# power.net
KiCad netlist of a schematic drawn in Altium Designer
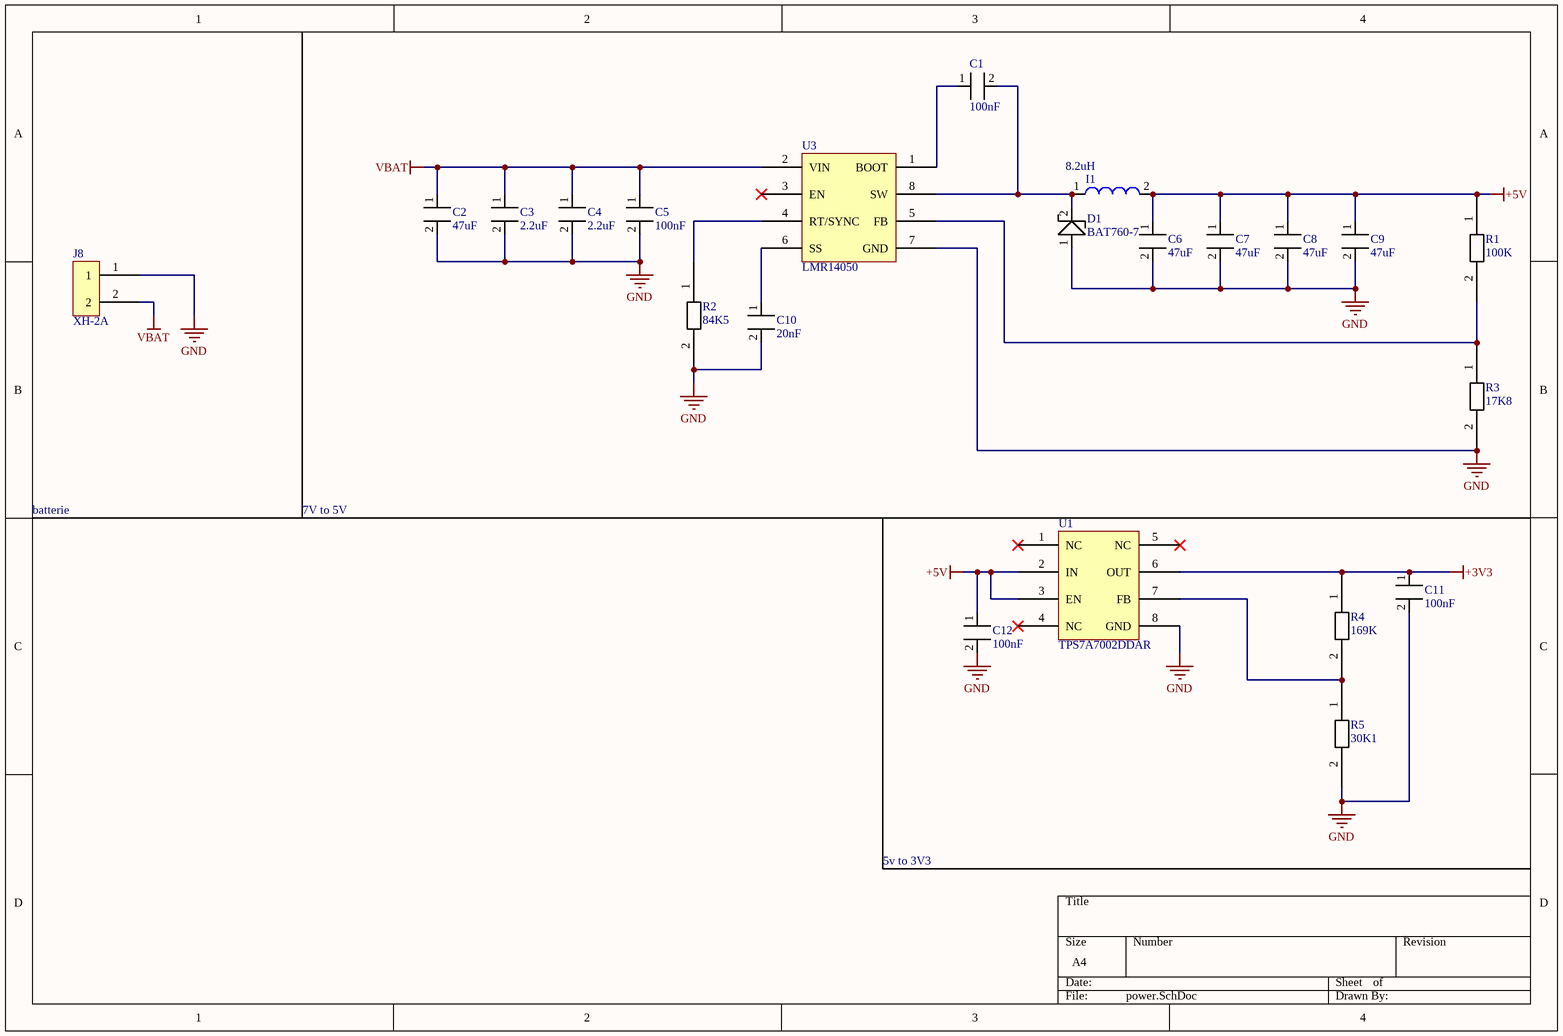
[diagram p0: power.SchDoc]

(export (version "E")
  (design (tool "Eeschema 10.0.6"))
  (components
    (comp (ref "C1") (value "100nF") (footprint "Condo") (libsource (lib "Schlib1") (part "CAPA")))
    (comp (ref "C2") (value "47uF") (footprint "Condo") (libsource (lib "Schlib1") (part "CAPA")))
    (comp (ref "C3") (value "2.2uF") (footprint "Condo") (libsource (lib "Schlib1") (part "CAPA")))
    (comp (ref "C4") (value "2.2uF") (footprint "Condo") (libsource (lib "Schlib1") (part "CAPA")))
    (comp (ref "C5") (value "100nF") (footprint "Condo") (libsource (lib "Schlib1") (part "CAPA")))
    (comp (ref "C6") (value "47uF") (footprint "Condo") (libsource (lib "Schlib1") (part "CAPA")))
    (comp (ref "C7") (value "47uF") (footprint "Condo") (libsource (lib "Schlib1") (part "CAPA")))
    (comp (ref "C8") (value "47uF") (footprint "Condo") (libsource (lib "Schlib1") (part "CAPA")))
    (comp (ref "C9") (value "47uF") (footprint "Condo") (libsource (lib "Schlib1") (part "CAPA")))
    (comp (ref "C10") (value "20nF") (footprint "Condo") (libsource (lib "Schlib1") (part "CAPA")))
    (comp (ref "C11") (value "100nF") (footprint "Condo") (libsource (lib "Schlib1") (part "CAPA")))
    (comp (ref "C12") (value "100nF") (footprint "Condo") (libsource (lib "Schlib1") (part "CAPA")))
    (comp (ref "D1") (value "BAT760-7") (footprint "BAT760-7") (libsource (lib "Schlib1") (part "BAT760-7")))
    (comp (ref "I1")
      (value "8.2uH")
      (footprint "ILSB0805ER8R2K")
      (description "ILSB0805ER8R2K")
      (libsource (lib "Schlib1") (part "ILSB0805ER8R2K"))
    )
    (comp (ref "J8") (value "XH-2A") (footprint "XH-2A") (libsource (lib "Schlib1") (part "XH-2A")))
    (comp (ref "R1") (value "100K") (footprint "Resistor") (libsource (lib "Schlib1") (part "Resistor")))
    (comp (ref "R2") (value "84K5") (footprint "Resistor") (libsource (lib "Schlib1") (part "Resistor")))
    (comp (ref "R3") (value "17K8") (footprint "Resistor") (libsource (lib "Schlib1") (part "Resistor")))
    (comp (ref "R4") (value "169K") (footprint "Resistor") (libsource (lib "Schlib1") (part "Resistor")))
    (comp (ref "R5") (value "30K1") (footprint "Resistor") (libsource (lib "Schlib1") (part "Resistor")))
    (comp (ref "U1")
      (value "TPS7A7002DDAR")
      (footprint "TPS7A7002DDAR")
      (libsource (lib "Schlib1") (part "TPS7A7002DDAR"))
    )
    (comp (ref "U3") (value "LMR14050") (footprint "LMR14050") (libsource (lib "Schlib1") (part "LMR14050")))
  )
  (nets
    (net (code "1") (name "+3V3") (class "Default")
      (node (ref "C11") (pin "1") (pinfunction "IN_1") (pintype "passive"))
      (node (ref "R4") (pin "1") (pinfunction "1_1") (pintype "passive"))
      (node (ref "U1") (pin "6") (pinfunction "OUT_6") (pintype "passive"))
    )
    (net (code "2") (name "+5V") (class "Default")
      (node (ref "C12") (pin "1") (pinfunction "IN_1") (pintype "passive"))
      (node (ref "C6") (pin "1") (pinfunction "IN_1") (pintype "passive"))
      (node (ref "C7") (pin "1") (pinfunction "IN_1") (pintype "passive"))
      (node (ref "C8") (pin "1") (pinfunction "IN_1") (pintype "passive"))
      (node (ref "C9") (pin "1") (pinfunction "IN_1") (pintype "passive"))
      (node (ref "I1") (pin "2") (pinfunction "2_2") (pintype "passive"))
      (node (ref "R1") (pin "1") (pinfunction "1_1") (pintype "passive"))
      (node (ref "U1") (pin "2") (pinfunction "IN_2") (pintype "passive"))
      (node (ref "U1") (pin "3") (pinfunction "EN_3") (pintype "passive"))
    )
    (net (code "3") (name "GND") (class "Default")
      (node (ref "C10") (pin "2") (pinfunction "OUT_2") (pintype "passive"))
      (node (ref "C11") (pin "2") (pinfunction "OUT_2") (pintype "passive"))
      (node (ref "C12") (pin "2") (pinfunction "OUT_2") (pintype "passive"))
      (node (ref "C2") (pin "2") (pinfunction "OUT_2") (pintype "passive"))
      (node (ref "C3") (pin "2") (pinfunction "OUT_2") (pintype "passive"))
      (node (ref "C4") (pin "2") (pinfunction "OUT_2") (pintype "passive"))
      (node (ref "C5") (pin "2") (pinfunction "OUT_2") (pintype "passive"))
      (node (ref "C6") (pin "2") (pinfunction "OUT_2") (pintype "passive"))
      (node (ref "C7") (pin "2") (pinfunction "OUT_2") (pintype "passive"))
      (node (ref "C8") (pin "2") (pinfunction "OUT_2") (pintype "passive"))
      (node (ref "C9") (pin "2") (pinfunction "OUT_2") (pintype "passive"))
      (node (ref "D1") (pin "1") (pinfunction "1_1") (pintype "passive"))
      (node (ref "J8") (pin "1") (pinfunction "1_1") (pintype "passive"))
      (node (ref "R2") (pin "2") (pinfunction "2_2") (pintype "passive"))
      (node (ref "R3") (pin "2") (pinfunction "2_2") (pintype "passive"))
      (node (ref "R5") (pin "2") (pinfunction "2_2") (pintype "passive"))
      (node (ref "U1") (pin "8") (pinfunction "GND_8") (pintype "passive"))
      (node (ref "U3") (pin "7") (pinfunction "GND_7") (pintype "passive"))
    )
    (net (code "4") (name "Net-(C1-IN)") (class "Default")
      (node (ref "C1") (pin "1") (pinfunction "IN_1") (pintype "passive"))
      (node (ref "U3") (pin "1") (pinfunction "BOOT_1") (pintype "passive"))
    )
    (net (code "5") (name "Net-(C1-OUT)") (class "Default")
      (node (ref "C1") (pin "2") (pinfunction "OUT_2") (pintype "passive"))
      (node (ref "D1") (pin "2") (pinfunction "2_2") (pintype "passive"))
      (node (ref "I1") (pin "1") (pinfunction "1_1") (pintype "passive"))
      (node (ref "U3") (pin "8") (pinfunction "SW_8") (pintype "passive"))
    )
    (net (code "6") (name "Net-(C10-IN)") (class "Default")
      (node (ref "C10") (pin "1") (pinfunction "IN_1") (pintype "passive"))
      (node (ref "U3") (pin "6") (pinfunction "SS_6") (pintype "passive"))
    )
    (net (code "7") (name "Net-(U1-FB)") (class "Default")
      (node (ref "R4") (pin "2") (pinfunction "2_2") (pintype "passive"))
      (node (ref "R5") (pin "1") (pinfunction "1_1") (pintype "passive"))
      (node (ref "U1") (pin "7") (pinfunction "FB_7") (pintype "passive"))
    )
    (net (code "8") (name "Net-(U3-FB)") (class "Default")
      (node (ref "R1") (pin "2") (pinfunction "2_2") (pintype "passive"))
      (node (ref "R3") (pin "1") (pinfunction "1_1") (pintype "passive"))
      (node (ref "U3") (pin "5") (pinfunction "FB_5") (pintype "passive"))
    )
    (net (code "9") (name "Net-(U3-RT{slash}SYNC)") (class "Default")
      (node (ref "R2") (pin "1") (pinfunction "1_1") (pintype "passive"))
      (node (ref "U3") (pin "4") (pinfunction "RT/SYNC_4") (pintype "passive"))
    )
    (net (code "10") (name "VBAT") (class "Default")
      (node (ref "C2") (pin "1") (pinfunction "IN_1") (pintype "passive"))
      (node (ref "C3") (pin "1") (pinfunction "IN_1") (pintype "passive"))
      (node (ref "C4") (pin "1") (pinfunction "IN_1") (pintype "passive"))
      (node (ref "C5") (pin "1") (pinfunction "IN_1") (pintype "passive"))
      (node (ref "J8") (pin "2") (pinfunction "2_2") (pintype "passive"))
      (node (ref "U3") (pin "2") (pinfunction "VIN_2") (pintype "passive"))
    )
    (net (code "11") (name "unconnected-(U1-NC-Pad1)") (class "Default")
      (node (ref "U1") (pin "1") (pinfunction "NC_1") (pintype "passive+no_connect"))
    )
    (net (code "12") (name "unconnected-(U1-NC-Pad4)") (class "Default")
      (node (ref "U1") (pin "4") (pinfunction "NC_4") (pintype "passive+no_connect"))
    )
    (net (code "13") (name "unconnected-(U1-NC-Pad5)") (class "Default")
      (node (ref "U1") (pin "5") (pinfunction "NC_5") (pintype "passive+no_connect"))
    )
    (net (code "14") (name "unconnected-(U3-EN-Pad3)") (class "Default")
      (node (ref "U3") (pin "3") (pinfunction "EN_3") (pintype "passive+no_connect"))
    )
  )
)
